# Grove_expansion_v5.net
KiCad netlist of a schematic drawn in EAGLE
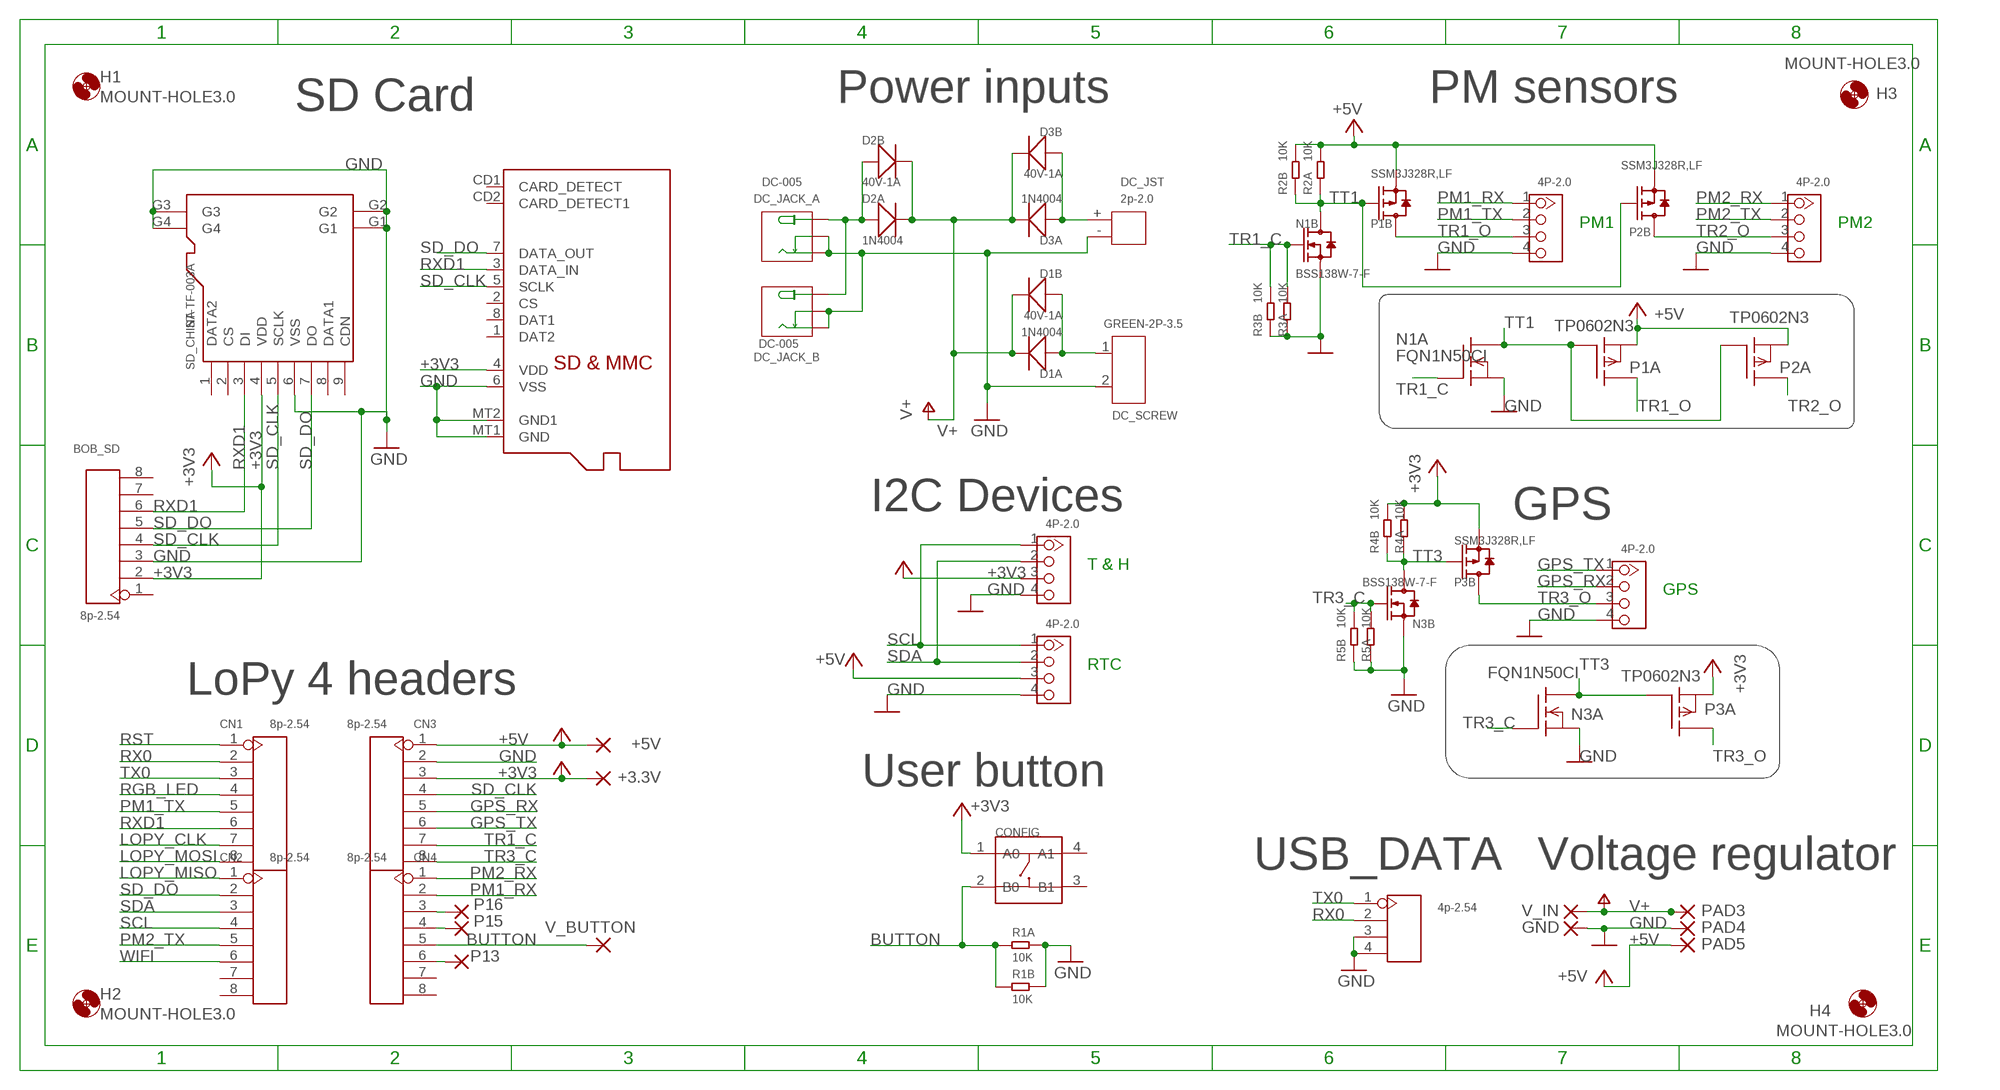
[diagram p0: schematic, sheet 1]

(export (version "E")
  (design (tool "Eeschema 10.0.6"))
  (components
    (comp (ref "+3.3V")
      (value "3.3V")
      (footprint "eagle-import:2,15_1,0")
      (libsource (lib "eagle-import") (part "2,15/1,0"))
    )
    (comp (ref "+5V")
      (value "5V")
      (footprint "eagle-import:2,15_1,0")
      (libsource (lib "eagle-import") (part "2,15/1,0"))
    )
    (comp (ref "BOB_SD")
      (value "8p-2.54")
      (footprint "eagle-import:H8-2.54")
      (fields (field (name "MPN") "F185-1108A1BSYC1"))
      (libsource (lib "eagle-import") (part "OPL_Connector_8004395_DIP-BLACK-FEMALE-HEADER-VERT(8P-2.54)"))
    )
    (comp (ref "CN1")
      (value "8p-2.54")
      (footprint "eagle-import:H8-2.54")
      (fields (field (name "MPN") "F185-1108A1BSYC1"))
      (libsource (lib "eagle-import") (part "DIP-BLACK-FEMALE-HEADER-VERT(8P-2.54)"))
    )
    (comp (ref "CN2")
      (value "8p-2.54")
      (footprint "eagle-import:H8-2.54")
      (fields (field (name "MPN") "F185-1108A1BSYC1"))
      (libsource (lib "eagle-import") (part "DIP-BLACK-FEMALE-HEADER-VERT(8P-2.54)"))
    )
    (comp (ref "CN3")
      (value "8p-2.54")
      (footprint "eagle-import:H8-2.54")
      (fields (field (name "MPN") "F185-1108A1BSYC1"))
      (libsource (lib "eagle-import") (part "DIP-BLACK-FEMALE-HEADER-VERT(8P-2.54)"))
    )
    (comp (ref "CN4")
      (value "8p-2.54")
      (footprint "eagle-import:H8-2.54")
      (fields (field (name "MPN") "F185-1108A1BSYC1"))
      (libsource (lib "eagle-import") (part "DIP-BLACK-FEMALE-HEADER-VERT(8P-2.54)"))
    )
    (comp (ref "CONFIG")
      (value "DIP-SWITCH-TACTILE-SPST-NO/TS-1109(4P-D6.0MM)'TS-1109'")
      (footprint "eagle-import:SW4-6.0X6.0X5.0MM")
      (libsource (lib "eagle-import") (part "DIP-SWITCH-TACTILE-SPST-NO/TS-1109(4P-D6.0MM)'TS-1109'"))
    )
    (comp (ref "D1A")
      (value "1N4004")
      (footprint "eagle-import:DO-41")
      (libsource (lib "eagle-import") (part "DIP-DIODE-400V-1A(DO-41)"))
    )
    (comp (ref "D1B")
      (value "40V-1A")
      (footprint "eagle-import:DO-214AC")
      (fields (field (name "MPN") "1N5819"))
      (libsource (lib "eagle-import") (part "SMD-DIODE-SCHOTTKY-40V-1A(DO-214AC)"))
    )
    (comp (ref "D2A")
      (value "1N4004")
      (footprint "eagle-import:DO-41")
      (libsource (lib "eagle-import") (part "DIP-DIODE-400V-1A(DO-41)"))
    )
    (comp (ref "D2B")
      (value "40V-1A")
      (footprint "eagle-import:DO-214AC")
      (fields (field (name "MPN") "1N5819"))
      (libsource (lib "eagle-import") (part "SMD-DIODE-SCHOTTKY-40V-1A(DO-214AC)"))
    )
    (comp (ref "D3A")
      (value "1N4004")
      (footprint "eagle-import:DO-41")
      (libsource (lib "eagle-import") (part "DIP-DIODE-400V-1A(DO-41)"))
    )
    (comp (ref "D3B")
      (value "40V-1A")
      (footprint "eagle-import:DO-214AC")
      (fields (field (name "MPN") "1N5819"))
      (libsource (lib "eagle-import") (part "SMD-DIODE-SCHOTTKY-40V-1A(DO-214AC)"))
    )
    (comp (ref "DC_JACK_A")
      (value "DC-005")
      (footprint "eagle-import:DCJ3P-14.2X11.0X9.0MM")
      (libsource (lib "eagle-import") (part "CONN-POWER-JACK-2.1MM(DC-005)"))
    )
    (comp (ref "DC_JACK_B")
      (value "DC-005")
      (footprint "eagle-import:DCJ3P-14.2X11.0X9.0MM")
      (libsource (lib "eagle-import") (part "CONN-POWER-JACK-2.1MM(DC-005)"))
    )
    (comp (ref "DC_JST")
      (value "2p-2.0")
      (footprint "eagle-import:H2-2.0-6X4.5MM")
      (libsource (lib "eagle-import") (part "DIP-JST-2P-2.0"))
    )
    (comp (ref "DC_SCREW")
      (value "GREEN-2P-3.5")
      (footprint "eagle-import:H2-3.5-7.0X7.0MM")
      (libsource (lib "eagle-import") (part "SCREW-TERMINAL-GREEN(2P-3.5)"))
    )
    (comp (ref "GND")
      (value "0V")
      (footprint "eagle-import:2,15_1,0")
      (libsource (lib "eagle-import") (part "2,15/1,0"))
    )
    (comp (ref "GPS-(DIG)")
      (value "4P-2.0")
      (footprint "eagle-import:HW4-2.0")
      (libsource (lib "eagle-import") (part "GROVE-CONNECTOR-DIP(4P-2.0)"))
    )
    (comp (ref "H1")
      (value "MOUNT-HOLE3.0")
      (footprint "eagle-import:3,0")
      (libsource (lib "eagle-import") (part "MOUNT-HOLE3.0"))
    )
    (comp (ref "H2")
      (value "MOUNT-HOLE3.0")
      (footprint "eagle-import:3,0")
      (libsource (lib "eagle-import") (part "MOUNT-HOLE3.0"))
    )
    (comp (ref "H3")
      (value "MOUNT-HOLE3.0")
      (footprint "eagle-import:3,0")
      (libsource (lib "eagle-import") (part "MOUNT-HOLE3.0"))
    )
    (comp (ref "H4")
      (value "MOUNT-HOLE3.0")
      (footprint "eagle-import:3,0")
      (libsource (lib "eagle-import") (part "MOUNT-HOLE3.0"))
    )
    (comp (ref "N1A")
      (value "FQN1N50CI")
      (footprint "eagle-import:TO92-INLINE")
      (libsource (lib "eagle-import") (part "FQN1N50CI"))
    )
    (comp (ref "N1B")
      (value "BSS138W-7-F")
      (footprint "eagle-import:SOT-23")
      (libsource (lib "eagle-import") (part "SMD-MOSFET-N-CH-50V-200MA-BSS138W-7-F(SOT-23)"))
    )
    (comp (ref "N3A")
      (value "FQN1N50CI")
      (footprint "eagle-import:TO92-INLINE")
      (libsource (lib "eagle-import") (part "FQN1N50CI"))
    )
    (comp (ref "N3B")
      (value "BSS138W-7-F")
      (footprint "eagle-import:SOT-23")
      (libsource (lib "eagle-import") (part "SMD-MOSFET-N-CH-50V-200MA-BSS138W-7-F(SOT-23)"))
    )
    (comp (ref "P1A")
      (value "TP0602N3")
      (footprint "eagle-import:TO-92")
      (libsource (lib "eagle-import") (part "TP0602N3"))
    )
    (comp (ref "P1B")
      (value "SSM3J328R,LF")
      (footprint "eagle-import:SOT-23")
      (libsource (lib "eagle-import") (part "SMD-MOSFET-P-CH-20V-6A-SSM3J328R(SOT-23)"))
    )
    (comp (ref "P2A")
      (value "TP0602N3")
      (footprint "eagle-import:TO-92")
      (libsource (lib "eagle-import") (part "TP0602N3"))
    )
    (comp (ref "P2B")
      (value "SSM3J328R,LF")
      (footprint "eagle-import:SOT-23")
      (libsource (lib "eagle-import") (part "SMD-MOSFET-P-CH-20V-6A-SSM3J328R(SOT-23)"))
    )
    (comp (ref "P3A")
      (value "TP0602N3")
      (footprint "eagle-import:TO-92")
      (libsource (lib "eagle-import") (part "TP0602N3"))
    )
    (comp (ref "P3B")
      (value "SSM3J328R,LF")
      (footprint "eagle-import:SOT-23")
      (libsource (lib "eagle-import") (part "SMD-MOSFET-P-CH-20V-6A-SSM3J328R(SOT-23)"))
    )
    (comp (ref "P13")
      (value "2,15/1,0")
      (footprint "eagle-import:2,15_1,0")
      (libsource (lib "eagle-import") (part "2,15/1,0"))
    )
    (comp (ref "P15")
      (value "2,15/1,0")
      (footprint "eagle-import:2,15_1,0")
      (libsource (lib "eagle-import") (part "2,15/1,0"))
    )
    (comp (ref "P16")
      (value "2,15/1,0")
      (footprint "eagle-import:2,15_1,0")
      (libsource (lib "eagle-import") (part "2,15/1,0"))
    )
    (comp (ref "PAD3")
      (value "12V")
      (footprint "eagle-import:1,6_0,8")
      (libsource (lib "eagle-import") (part "1,6/0,8"))
    )
    (comp (ref "PAD4")
      (value "0V")
      (footprint "eagle-import:1,6_0,8")
      (libsource (lib "eagle-import") (part "1,6/0,8"))
    )
    (comp (ref "PAD5")
      (value "5V")
      (footprint "eagle-import:1,6_0,8")
      (libsource (lib "eagle-import") (part "1,6/0,8"))
    )
    (comp (ref "PM1-(UART)")
      (value "4P-2.0")
      (footprint "eagle-import:HW4-2.0")
      (libsource (lib "eagle-import") (part "GROVE-CONNECTOR-DIP(4P-2.0)"))
    )
    (comp (ref "PM2-(UART)")
      (value "4P-2.0")
      (footprint "eagle-import:HW4-2.0")
      (libsource (lib "eagle-import") (part "GROVE-CONNECTOR-DIP(4P-2.0)"))
    )
    (comp (ref "R1A")
      (value "10K")
      (footprint "eagle-import:PR-D2.3XL6.5MM")
      (fields (field (name "MPN") "FHCFR-1/4W-103J"))
      (libsource (lib "eagle-import") (part "DIP-RES-10K-5%-1/4W(PR-D2.3XL6.5MM)"))
    )
    (comp (ref "R1B")
      (value "10K")
      (footprint "eagle-import:R0603")
      (fields (field (name "MPN") "RC0603FR-0710KL"))
      (libsource (lib "eagle-import") (part "SMD-RES-10K-1%-1/10W(0603)"))
    )
    (comp (ref "R2A")
      (value "10K")
      (footprint "eagle-import:PR-D2.3XL6.5MM")
      (fields (field (name "MPN") "FHCFR-1/4W-103J"))
      (libsource (lib "eagle-import") (part "DIP-RES-10K-5%-1/4W(PR-D2.3XL6.5MM)"))
    )
    (comp (ref "R2B")
      (value "10K")
      (footprint "eagle-import:R0603")
      (fields (field (name "MPN") "RC0603FR-0710KL"))
      (libsource (lib "eagle-import") (part "SMD-RES-10K-1%-1/10W(0603)"))
    )
    (comp (ref "R3A")
      (value "10K")
      (footprint "eagle-import:PR-D2.3XL6.5MM")
      (fields (field (name "MPN") "FHCFR-1/4W-103J"))
      (libsource (lib "eagle-import") (part "DIP-RES-10K-5%-1/4W(PR-D2.3XL6.5MM)"))
    )
    (comp (ref "R3B")
      (value "10K")
      (footprint "eagle-import:R0603")
      (fields (field (name "MPN") "RC0603FR-0710KL"))
      (libsource (lib "eagle-import") (part "SMD-RES-10K-1%-1/10W(0603)"))
    )
    (comp (ref "R4A")
      (value "10K")
      (footprint "eagle-import:PR-D2.3XL6.5MM")
      (fields (field (name "MPN") "FHCFR-1/4W-103J"))
      (libsource (lib "eagle-import") (part "DIP-RES-10K-5%-1/4W(PR-D2.3XL6.5MM)"))
    )
    (comp (ref "R4B")
      (value "10K")
      (footprint "eagle-import:R0603")
      (fields (field (name "MPN") "RC0603FR-0710KL"))
      (libsource (lib "eagle-import") (part "SMD-RES-10K-1%-1/10W(0603)"))
    )
    (comp (ref "R5A")
      (value "10K")
      (footprint "eagle-import:PR-D2.3XL6.5MM")
      (fields (field (name "MPN") "FHCFR-1/4W-103J"))
      (libsource (lib "eagle-import") (part "DIP-RES-10K-5%-1/4W(PR-D2.3XL6.5MM)"))
    )
    (comp (ref "R5B")
      (value "10K")
      (footprint "eagle-import:R0603")
      (fields (field (name "MPN") "RC0603FR-0710KL"))
      (libsource (lib "eagle-import") (part "SMD-RES-10K-1%-1/10W(0603)"))
    )
    (comp (ref "RTC-(I2C)")
      (value "4P-2.0")
      (footprint "eagle-import:HW4-2.0")
      (libsource (lib "eagle-import") (part "GROVE-CONNECTOR-DIP(4P-2.0)"))
    )
    (comp (ref "SD_CHINA")
      (value "ST-TF-003A")
      (footprint "eagle-import:MICRO-SD9+4P-SMD-16.1X14.5X1.85MM")
      (libsource (lib "eagle-import") (part "MICRO-SD-CARD-SOCKET-9P(ST-TF-003A)"))
    )
    (comp (ref "SD_UK")
      (value "MICROSD")
      (footprint "eagle-import:MICROSD")
      (libsource (lib "eagle-import") (part "MICROSD"))
    )
    (comp (ref "TH-(I2C)")
      (value "4P-2.0")
      (footprint "eagle-import:HW4-2.0")
      (libsource (lib "eagle-import") (part "GROVE-CONNECTOR-DIP(4P-2.0)"))
    )
    (comp (ref "USB_DATA")
      (value "4p-2.54")
      (footprint "eagle-import:H4-2.54")
      (fields (field (name "MPN") "F185-1104A1BSYA1"))
      (libsource (lib "eagle-import") (part "DIP-BLACK-FEMALE-HEADER-VERT(4P-2.54)"))
    )
    (comp (ref "V_BUTTON")
      (value "3.3V")
      (footprint "eagle-import:2,15_1,0")
      (libsource (lib "eagle-import") (part "2,15/1,0"))
    )
    (comp (ref "V_IN")
      (value "12V")
      (footprint "eagle-import:2,15_1,0")
      (libsource (lib "eagle-import") (part "2,15/1,0"))
    )
  )
  (nets
    (net (code "1") (name "+3V3") (class "Default")
      (node (ref "+3.3V") (pin "1") (pinfunction "P_1") (pintype "passive"))
      (node (ref "BOB_SD") (pin "2") (pinfunction "2_2") (pintype "bidirectional"))
      (node (ref "CN3") (pin "3") (pinfunction "3_3") (pintype "bidirectional"))
      (node (ref "CONFIG") (pin "1") (pinfunction "A0_1") (pintype "bidirectional"))
      (node (ref "P3A") (pin "1") (pinfunction "S_1") (pintype "passive"))
      (node (ref "P3B") (pin "2") (pinfunction "S_2") (pintype "passive"))
      (node (ref "R4A") (pin "2") (pinfunction "2_2") (pintype "passive"))
      (node (ref "R4B") (pin "2") (pinfunction "2_2") (pintype "passive"))
      (node (ref "SD_CHINA") (pin "4") (pinfunction "VDD_4") (pintype "bidirectional"))
      (node (ref "SD_UK") (pin "4") (pinfunction "VDD_4") (pintype "power_in"))
      (node (ref "TH-(I2C)") (pin "3") (pinfunction "3_3") (pintype "bidirectional"))
    )
    (net (code "2") (name "+5V") (class "Default")
      (node (ref "+5V") (pin "1") (pinfunction "P_1") (pintype "passive"))
      (node (ref "CN3") (pin "1") (pinfunction "1_1") (pintype "bidirectional"))
      (node (ref "P1A") (pin "1") (pinfunction "S_1") (pintype "passive"))
      (node (ref "P1B") (pin "2") (pinfunction "S_2") (pintype "passive"))
      (node (ref "P2A") (pin "1") (pinfunction "S_1") (pintype "passive"))
      (node (ref "P2B") (pin "2") (pinfunction "S_2") (pintype "passive"))
      (node (ref "PAD5") (pin "1") (pinfunction "P_1") (pintype "passive"))
      (node (ref "R2A") (pin "2") (pinfunction "2_2") (pintype "passive"))
      (node (ref "R2B") (pin "2") (pinfunction "2_2") (pintype "passive"))
      (node (ref "RTC-(I2C)") (pin "3") (pinfunction "3_3") (pintype "bidirectional"))
    )
    (net (code "3") (name "BUTTON") (class "Default")
      (node (ref "CN4") (pin "5") (pinfunction "5_5") (pintype "bidirectional"))
      (node (ref "CONFIG") (pin "2") (pinfunction "B0_2") (pintype "bidirectional"))
      (node (ref "R1A") (pin "1") (pinfunction "1_1") (pintype "passive"))
      (node (ref "R1B") (pin "1") (pinfunction "1_1") (pintype "passive"))
      (node (ref "V_BUTTON") (pin "1") (pinfunction "P_1") (pintype "passive"))
    )
    (net (code "4") (name "GND") (class "Default")
      (node (ref "BOB_SD") (pin "3") (pinfunction "3_3") (pintype "bidirectional"))
      (node (ref "CN3") (pin "2") (pinfunction "2_2") (pintype "bidirectional"))
      (node (ref "DC_JACK_A") (pin "-1") (pinfunction "-_-1") (pintype "bidirectional"))
      (node (ref "DC_JACK_A") (pin "-2") (pinfunction "CDN_-2") (pintype "bidirectional"))
      (node (ref "DC_JACK_B") (pin "-1") (pinfunction "-_-1") (pintype "bidirectional"))
      (node (ref "DC_JACK_B") (pin "-2") (pinfunction "CDN_-2") (pintype "bidirectional"))
      (node (ref "DC_JST") (pin "-") (pinfunction "P$2_-") (pintype "bidirectional"))
      (node (ref "DC_SCREW") (pin "2") (pinfunction "2_2") (pintype "bidirectional"))
      (node (ref "GND") (pin "1") (pinfunction "P_1") (pintype "passive"))
      (node (ref "GPS-(DIG)") (pin "4") (pinfunction "4_4") (pintype "bidirectional"))
      (node (ref "N1A") (pin "3") (pinfunction "S_3") (pintype "passive"))
      (node (ref "N1B") (pin "2") (pinfunction "S_2") (pintype "passive"))
      (node (ref "N3A") (pin "3") (pinfunction "S_3") (pintype "passive"))
      (node (ref "N3B") (pin "2") (pinfunction "S_2") (pintype "passive"))
      (node (ref "PAD4") (pin "1") (pinfunction "P_1") (pintype "passive"))
      (node (ref "PM1-(UART)") (pin "4") (pinfunction "4_4") (pintype "bidirectional"))
      (node (ref "PM2-(UART)") (pin "4") (pinfunction "4_4") (pintype "bidirectional"))
      (node (ref "R1A") (pin "2") (pinfunction "2_2") (pintype "passive"))
      (node (ref "R1B") (pin "2") (pinfunction "2_2") (pintype "passive"))
      (node (ref "R3A") (pin "1") (pinfunction "1_1") (pintype "passive"))
      (node (ref "R3B") (pin "1") (pinfunction "1_1") (pintype "passive"))
      (node (ref "R5A") (pin "1") (pinfunction "1_1") (pintype "passive"))
      (node (ref "R5B") (pin "1") (pinfunction "1_1") (pintype "passive"))
      (node (ref "RTC-(I2C)") (pin "4") (pinfunction "4_4") (pintype "bidirectional"))
      (node (ref "SD_CHINA") (pin "6") (pinfunction "VSS_6") (pintype "bidirectional"))
      (node (ref "SD_CHINA") (pin "G1") (pinfunction "G1_G1") (pintype "bidirectional"))
      (node (ref "SD_CHINA") (pin "G2") (pinfunction "G2_G2") (pintype "bidirectional"))
      (node (ref "SD_CHINA") (pin "G3") (pinfunction "G3_G3") (pintype "bidirectional"))
      (node (ref "SD_CHINA") (pin "G4") (pinfunction "G4_G4") (pintype "bidirectional"))
      (node (ref "SD_UK") (pin "6") (pinfunction "VSS_6") (pintype "power_in"))
      (node (ref "SD_UK") (pin "MT1") (pinfunction "GND_MT1") (pintype "power_in"))
      (node (ref "SD_UK") (pin "MT2") (pinfunction "GND1_MT2") (pintype "power_in"))
      (node (ref "TH-(I2C)") (pin "4") (pinfunction "4_4") (pintype "bidirectional"))
      (node (ref "USB_DATA") (pin "3") (pinfunction "P$3_3") (pintype "bidirectional"))
      (node (ref "USB_DATA") (pin "4") (pinfunction "P$4_4") (pintype "bidirectional"))
    )
    (net (code "5") (name "GPS_RX") (class "Default")
      (node (ref "CN3") (pin "5") (pinfunction "5_5") (pintype "bidirectional"))
      (node (ref "GPS-(DIG)") (pin "2") (pinfunction "2_2") (pintype "bidirectional"))
    )
    (net (code "6") (name "GPS_TX") (class "Default")
      (node (ref "CN3") (pin "6") (pinfunction "6_6") (pintype "bidirectional"))
      (node (ref "GPS-(DIG)") (pin "1") (pinfunction "1_1") (pintype "bidirectional"))
    )
    (net (code "7") (name "LOPY_CLK") (class "Default")
      (node (ref "CN1") (pin "7") (pinfunction "7_7") (pintype "bidirectional"))
    )
    (net (code "8") (name "LOPY_MISO") (class "Default")
      (node (ref "CN2") (pin "1") (pinfunction "1_1") (pintype "bidirectional"))
    )
    (net (code "9") (name "LOPY_MOSI") (class "Default")
      (node (ref "CN1") (pin "8") (pinfunction "8_8") (pintype "bidirectional"))
    )
    (net (code "10") (name "Net-(D1A-+)") (class "Default")
      (node (ref "D1A") (pin "1") (pinfunction "+_1") (pintype "passive"))
      (node (ref "D1B") (pin "1") (pinfunction "+_1") (pintype "passive"))
      (node (ref "DC_SCREW") (pin "1") (pinfunction "1_1") (pintype "bidirectional"))
    )
    (net (code "11") (name "Net-(D2A-+)") (class "Default")
      (node (ref "D2A") (pin "1") (pinfunction "+_1") (pintype "passive"))
      (node (ref "D2B") (pin "1") (pinfunction "+_1") (pintype "passive"))
      (node (ref "DC_JACK_A") (pin "+") (pinfunction "+_+") (pintype "bidirectional"))
      (node (ref "DC_JACK_B") (pin "+") (pinfunction "+_+") (pintype "bidirectional"))
    )
    (net (code "12") (name "Net-(D3A-+)") (class "Default")
      (node (ref "D3A") (pin "1") (pinfunction "+_1") (pintype "passive"))
      (node (ref "D3B") (pin "1") (pinfunction "+_1") (pintype "passive"))
      (node (ref "DC_JST") (pin "+") (pinfunction "P$1_+") (pintype "bidirectional"))
    )
    (net (code "13") (name "P13") (class "Default")
      (node (ref "CN4") (pin "6") (pinfunction "6_6") (pintype "bidirectional"))
      (node (ref "P13") (pin "1") (pinfunction "P_1") (pintype "passive"))
    )
    (net (code "14") (name "P15") (class "Default")
      (node (ref "CN4") (pin "4") (pinfunction "4_4") (pintype "bidirectional"))
      (node (ref "P15") (pin "1") (pinfunction "P_1") (pintype "passive"))
    )
    (net (code "15") (name "P16") (class "Default")
      (node (ref "CN4") (pin "3") (pinfunction "3_3") (pintype "bidirectional"))
      (node (ref "P16") (pin "1") (pinfunction "P_1") (pintype "passive"))
    )
    (net (code "16") (name "PM1_RX") (class "Default")
      (node (ref "CN4") (pin "2") (pinfunction "2_2") (pintype "bidirectional"))
      (node (ref "PM1-(UART)") (pin "1") (pinfunction "1_1") (pintype "bidirectional"))
    )
    (net (code "17") (name "PM1_TX") (class "Default")
      (node (ref "CN1") (pin "5") (pinfunction "5_5") (pintype "bidirectional"))
      (node (ref "PM1-(UART)") (pin "2") (pinfunction "2_2") (pintype "bidirectional"))
    )
    (net (code "18") (name "PM2_RX") (class "Default")
      (node (ref "CN4") (pin "1") (pinfunction "1_1") (pintype "bidirectional"))
      (node (ref "PM2-(UART)") (pin "1") (pinfunction "1_1") (pintype "bidirectional"))
    )
    (net (code "19") (name "PM2_TX") (class "Default")
      (node (ref "CN2") (pin "5") (pinfunction "5_5") (pintype "bidirectional"))
      (node (ref "PM2-(UART)") (pin "2") (pinfunction "2_2") (pintype "bidirectional"))
    )
    (net (code "20") (name "RGB_LED") (class "Default")
      (node (ref "CN1") (pin "4") (pinfunction "4_4") (pintype "bidirectional"))
    )
    (net (code "21") (name "RST") (class "Default")
      (node (ref "CN1") (pin "1") (pinfunction "1_1") (pintype "bidirectional"))
    )
    (net (code "22") (name "RX0") (class "Default")
      (node (ref "CN1") (pin "2") (pinfunction "2_2") (pintype "bidirectional"))
      (node (ref "USB_DATA") (pin "2") (pinfunction "P$2_2") (pintype "bidirectional"))
    )
    (net (code "23") (name "RXD1") (class "Default")
      (node (ref "BOB_SD") (pin "6") (pinfunction "6_6") (pintype "bidirectional"))
      (node (ref "CN1") (pin "6") (pinfunction "6_6") (pintype "bidirectional"))
      (node (ref "SD_CHINA") (pin "3") (pinfunction "DI_3") (pintype "bidirectional"))
      (node (ref "SD_UK") (pin "3") (pinfunction "DATA_IN_3") (pintype "input"))
    )
    (net (code "24") (name "SCL") (class "Default")
      (node (ref "CN2") (pin "4") (pinfunction "4_4") (pintype "bidirectional"))
      (node (ref "RTC-(I2C)") (pin "1") (pinfunction "1_1") (pintype "bidirectional"))
      (node (ref "TH-(I2C)") (pin "1") (pinfunction "1_1") (pintype "bidirectional"))
    )
    (net (code "25") (name "SDA") (class "Default")
      (node (ref "CN2") (pin "3") (pinfunction "3_3") (pintype "bidirectional"))
      (node (ref "RTC-(I2C)") (pin "2") (pinfunction "2_2") (pintype "bidirectional"))
      (node (ref "TH-(I2C)") (pin "2") (pinfunction "2_2") (pintype "bidirectional"))
    )
    (net (code "26") (name "SD_CLK") (class "Default")
      (node (ref "BOB_SD") (pin "4") (pinfunction "4_4") (pintype "bidirectional"))
      (node (ref "CN3") (pin "4") (pinfunction "4_4") (pintype "bidirectional"))
      (node (ref "SD_CHINA") (pin "5") (pinfunction "SCLK_5") (pintype "bidirectional"))
      (node (ref "SD_UK") (pin "5") (pinfunction "SCLK_5") (pintype "input"))
    )
    (net (code "27") (name "SD_DO") (class "Default")
      (node (ref "BOB_SD") (pin "5") (pinfunction "5_5") (pintype "bidirectional"))
      (node (ref "CN2") (pin "2") (pinfunction "2_2") (pintype "bidirectional"))
      (node (ref "SD_CHINA") (pin "7") (pinfunction "DO_7") (pintype "bidirectional"))
      (node (ref "SD_UK") (pin "7") (pinfunction "DATA_OUT_7") (pintype "output"))
    )
    (net (code "28") (name "TR1_C") (class "Default")
      (node (ref "CN3") (pin "7") (pinfunction "7_7") (pintype "bidirectional"))
      (node (ref "N1A") (pin "2") (pinfunction "G_2") (pintype "passive"))
      (node (ref "N1B") (pin "1") (pinfunction "G_1") (pintype "passive"))
      (node (ref "R3A") (pin "2") (pinfunction "2_2") (pintype "passive"))
      (node (ref "R3B") (pin "2") (pinfunction "2_2") (pintype "passive"))
    )
    (net (code "29") (name "TR1_O") (class "Default")
      (node (ref "P1A") (pin "3") (pinfunction "D_3") (pintype "passive"))
      (node (ref "P1B") (pin "3") (pinfunction "D_3") (pintype "passive"))
      (node (ref "PM1-(UART)") (pin "3") (pinfunction "3_3") (pintype "bidirectional"))
    )
    (net (code "30") (name "TR2_O") (class "Default")
      (node (ref "P2A") (pin "3") (pinfunction "D_3") (pintype "passive"))
      (node (ref "P2B") (pin "3") (pinfunction "D_3") (pintype "passive"))
      (node (ref "PM2-(UART)") (pin "3") (pinfunction "3_3") (pintype "bidirectional"))
    )
    (net (code "31") (name "TR3_C") (class "Default")
      (node (ref "CN3") (pin "8") (pinfunction "8_8") (pintype "bidirectional"))
      (node (ref "N3A") (pin "2") (pinfunction "G_2") (pintype "passive"))
      (node (ref "N3B") (pin "1") (pinfunction "G_1") (pintype "passive"))
      (node (ref "R5A") (pin "2") (pinfunction "2_2") (pintype "passive"))
      (node (ref "R5B") (pin "2") (pinfunction "2_2") (pintype "passive"))
    )
    (net (code "32") (name "TR3_O") (class "Default")
      (node (ref "GPS-(DIG)") (pin "3") (pinfunction "3_3") (pintype "bidirectional"))
      (node (ref "P3A") (pin "3") (pinfunction "D_3") (pintype "passive"))
      (node (ref "P3B") (pin "3") (pinfunction "D_3") (pintype "passive"))
    )
    (net (code "33") (name "TT1") (class "Default")
      (node (ref "N1A") (pin "1") (pinfunction "D_1") (pintype "passive"))
      (node (ref "N1B") (pin "3") (pinfunction "D_3") (pintype "passive"))
      (node (ref "P1A") (pin "2") (pinfunction "G_2") (pintype "passive"))
      (node (ref "P1B") (pin "1") (pinfunction "G_1") (pintype "passive"))
      (node (ref "P2A") (pin "2") (pinfunction "G_2") (pintype "passive"))
      (node (ref "P2B") (pin "1") (pinfunction "G_1") (pintype "passive"))
      (node (ref "R2A") (pin "1") (pinfunction "1_1") (pintype "passive"))
      (node (ref "R2B") (pin "1") (pinfunction "1_1") (pintype "passive"))
    )
    (net (code "34") (name "TT3") (class "Default")
      (node (ref "N3A") (pin "1") (pinfunction "D_1") (pintype "passive"))
      (node (ref "N3B") (pin "3") (pinfunction "D_3") (pintype "passive"))
      (node (ref "P3A") (pin "2") (pinfunction "G_2") (pintype "passive"))
      (node (ref "P3B") (pin "1") (pinfunction "G_1") (pintype "passive"))
      (node (ref "R4A") (pin "1") (pinfunction "1_1") (pintype "passive"))
      (node (ref "R4B") (pin "1") (pinfunction "1_1") (pintype "passive"))
    )
    (net (code "35") (name "TX0") (class "Default")
      (node (ref "CN1") (pin "3") (pinfunction "3_3") (pintype "bidirectional"))
      (node (ref "USB_DATA") (pin "1") (pinfunction "P$1_1") (pintype "bidirectional"))
    )
    (net (code "36") (name "V+") (class "Default")
      (node (ref "D1A") (pin "2") (pinfunction "-_2") (pintype "passive"))
      (node (ref "D1B") (pin "2") (pinfunction "-_2") (pintype "passive"))
      (node (ref "D2A") (pin "2") (pinfunction "-_2") (pintype "passive"))
      (node (ref "D2B") (pin "2") (pinfunction "-_2") (pintype "passive"))
      (node (ref "D3A") (pin "2") (pinfunction "-_2") (pintype "passive"))
      (node (ref "D3B") (pin "2") (pinfunction "-_2") (pintype "passive"))
      (node (ref "PAD3") (pin "1") (pinfunction "P_1") (pintype "passive"))
      (node (ref "V_IN") (pin "1") (pinfunction "P_1") (pintype "passive"))
    )
    (net (code "37") (name "WIFI") (class "Default")
      (node (ref "CN2") (pin "6") (pinfunction "6_6") (pintype "bidirectional"))
    )
    (net (code "38") (name "unconnected-(BOB_SD-Pad1)") (class "Default")
      (node (ref "BOB_SD") (pin "1") (pinfunction "1_1") (pintype "bidirectional"))
    )
    (net (code "39") (name "unconnected-(BOB_SD-Pad7)") (class "Default")
      (node (ref "BOB_SD") (pin "7") (pinfunction "7_7") (pintype "bidirectional"))
    )
    (net (code "40") (name "unconnected-(BOB_SD-Pad8)") (class "Default")
      (node (ref "BOB_SD") (pin "8") (pinfunction "8_8") (pintype "bidirectional"))
    )
    (net (code "41") (name "unconnected-(CN2-Pad7)") (class "Default")
      (node (ref "CN2") (pin "7") (pinfunction "7_7") (pintype "bidirectional"))
    )
    (net (code "42") (name "unconnected-(CN2-Pad8)") (class "Default")
      (node (ref "CN2") (pin "8") (pinfunction "8_8") (pintype "bidirectional"))
    )
    (net (code "43") (name "unconnected-(CN4-Pad7)") (class "Default")
      (node (ref "CN4") (pin "7") (pinfunction "7_7") (pintype "bidirectional"))
    )
    (net (code "44") (name "unconnected-(CN4-Pad8)") (class "Default")
      (node (ref "CN4") (pin "8") (pinfunction "8_8") (pintype "bidirectional"))
    )
    (net (code "45") (name "unconnected-(CONFIG-A1-Pad4)") (class "Default")
      (node (ref "CONFIG") (pin "4") (pinfunction "A1_4") (pintype "bidirectional"))
    )
    (net (code "46") (name "unconnected-(CONFIG-B1-Pad3)") (class "Default")
      (node (ref "CONFIG") (pin "3") (pinfunction "B1_3") (pintype "bidirectional"))
    )
    (net (code "47") (name "unconnected-(SD_CHINA-CDN-Pad9)") (class "Default")
      (node (ref "SD_CHINA") (pin "9") (pinfunction "CDN_9") (pintype "bidirectional"))
    )
    (net (code "48") (name "unconnected-(SD_CHINA-CS-Pad2)") (class "Default")
      (node (ref "SD_CHINA") (pin "2") (pinfunction "CS_2") (pintype "bidirectional"))
    )
    (net (code "49") (name "unconnected-(SD_CHINA-DATA1-Pad8)") (class "Default")
      (node (ref "SD_CHINA") (pin "8") (pinfunction "DATA1_8") (pintype "bidirectional"))
    )
    (net (code "50") (name "unconnected-(SD_CHINA-DATA2-Pad1)") (class "Default")
      (node (ref "SD_CHINA") (pin "1") (pinfunction "DATA2_1") (pintype "bidirectional"))
    )
    (net (code "51") (name "unconnected-(SD_UK-CARD_DETECT-PadCD1)") (class "Default")
      (node (ref "SD_UK") (pin "CD1") (pinfunction "CARD_DETECT_CD1") (pintype "passive"))
    )
    (net (code "52") (name "unconnected-(SD_UK-CARD_DETECT1-PadCD2)") (class "Default")
      (node (ref "SD_UK") (pin "CD2") (pinfunction "CARD_DETECT1_CD2") (pintype "passive"))
    )
    (net (code "53") (name "unconnected-(SD_UK-CS-Pad2)") (class "Default")
      (node (ref "SD_UK") (pin "2") (pinfunction "CS_2") (pintype "input"))
    )
    (net (code "54") (name "unconnected-(SD_UK-DAT1-Pad8)") (class "Default")
      (node (ref "SD_UK") (pin "8") (pinfunction "DAT1_8") (pintype "bidirectional"))
    )
    (net (code "55") (name "unconnected-(SD_UK-DAT2-Pad1)") (class "Default")
      (node (ref "SD_UK") (pin "1") (pinfunction "DAT2_1") (pintype "bidirectional"))
    )
  )
)
